# LDO_Regulator.net
KiCad netlist of a schematic drawn in Altium Designer
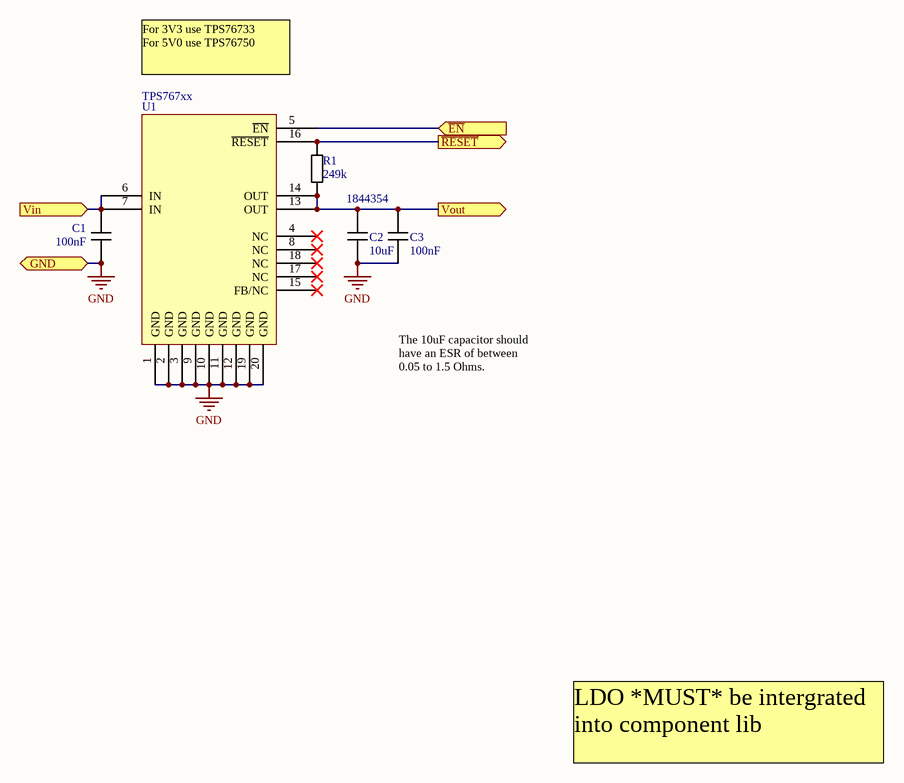
[diagram p0: LDO_Regulator.SchDoc]

(export (version "E")
  (design (tool "Eeschema 10.0.6"))
  (components
    (comp (ref "C1")
      (value "100nF")
      (footprint "0805 Cap")
      (description "0805 MLCC - X7R, 10%")
      (fields (field (name "Comment") "0805 Cap"))
      (libsource (lib "Schlib1") (part "0805 MLCC - X7R, 10%"))
    )
    (comp (ref "C2")
      (value "10uF")
      (footprint "1210 Cap")
      (description "1210 MLCC - X7R, 10%")
      (fields (field (name "SUPPLIER PART NUMBER 1") "1844354") (field (name "Comment") "1210 Cap"))
      (libsource (lib "Schlib1") (part "1210 MLCC - X7R, 10%"))
    )
    (comp (ref "C3")
      (value "100nF")
      (footprint "0805 Cap")
      (description "0805 MLCC - X7R, 10%")
      (fields (field (name "Comment") "0805 Cap"))
      (libsource (lib "Schlib1") (part "0805 MLCC - X7R, 10%"))
    )
    (comp (ref "R1")
      (value "249k")
      (footprint "0805 Resistor")
      (description "0805 Thick Film Resistor 1%")
      (fields (field (name "Comment") "0805 Resistor"))
      (libsource (lib "Schlib1") (part "0805 Thick Film Resistor 1%"))
    )
    (comp (ref "U1")
      (value "TPS767xx")
      (footprint "SOP-20 TPS76700")
      (description "LDO Regulator - ER")
      (libsource (lib "Schlib1") (part "TPS76700"))
    )
  )
  (nets
    (net (code "1") (name "/Vin") (class "Default")
      (node (ref "C1") (pin "2") (pinfunction "2_2") (pintype "passive"))
      (node (ref "U1") (pin "6") (pinfunction "IN_6") (pintype "passive"))
      (node (ref "U1") (pin "7") (pinfunction "IN_7") (pintype "passive"))
    )
    (net (code "2") (name "/Vout") (class "Default")
      (node (ref "C2") (pin "2") (pinfunction "2_2") (pintype "passive"))
      (node (ref "C3") (pin "2") (pinfunction "2_2") (pintype "passive"))
      (node (ref "R1") (pin "1") (pinfunction "1_1") (pintype "passive"))
      (node (ref "U1") (pin "13") (pinfunction "OUT_13") (pintype "passive"))
      (node (ref "U1") (pin "14") (pinfunction "OUT_14") (pintype "passive"))
    )
    (net (code "3") (name "/~{EN}") (class "Default")
      (node (ref "U1") (pin "5") (pinfunction "~{EN}_5") (pintype "passive"))
    )
    (net (code "4") (name "/~{RESET}") (class "Default")
      (node (ref "R1") (pin "2") (pinfunction "2_2") (pintype "passive"))
      (node (ref "U1") (pin "16") (pinfunction "~{RESET}_16") (pintype "passive"))
    )
    (net (code "5") (name "GND") (class "Default")
      (node (ref "C1") (pin "1") (pinfunction "1_1") (pintype "passive"))
      (node (ref "C2") (pin "1") (pinfunction "1_1") (pintype "passive"))
      (node (ref "C3") (pin "1") (pinfunction "1_1") (pintype "passive"))
      (node (ref "U1") (pin "1") (pinfunction "GND_1") (pintype "passive"))
      (node (ref "U1") (pin "10") (pinfunction "GND_10") (pintype "passive"))
      (node (ref "U1") (pin "11") (pinfunction "GND_11") (pintype "passive"))
      (node (ref "U1") (pin "12") (pinfunction "GND_12") (pintype "passive"))
      (node (ref "U1") (pin "19") (pinfunction "GND_19") (pintype "passive"))
      (node (ref "U1") (pin "2") (pinfunction "GND_2") (pintype "passive"))
      (node (ref "U1") (pin "20") (pinfunction "GND_20") (pintype "passive"))
      (node (ref "U1") (pin "3") (pinfunction "GND_3") (pintype "passive"))
      (node (ref "U1") (pin "9") (pinfunction "GND_9") (pintype "passive"))
    )
    (net (code "6") (name "unconnected-(U1-FB{slash}NC-Pad15)") (class "Default")
      (node (ref "U1") (pin "15") (pinfunction "FB/NC_15") (pintype "passive+no_connect"))
    )
    (net (code "7") (name "unconnected-(U1-NC-Pad4)") (class "Default")
      (node (ref "U1") (pin "4") (pinfunction "NC_4") (pintype "passive+no_connect"))
    )
    (net (code "8") (name "unconnected-(U1-NC-Pad8)") (class "Default")
      (node (ref "U1") (pin "8") (pinfunction "NC_8") (pintype "passive+no_connect"))
    )
    (net (code "9") (name "unconnected-(U1-NC-Pad17)") (class "Default")
      (node (ref "U1") (pin "17") (pinfunction "NC_17") (pintype "passive+no_connect"))
    )
    (net (code "10") (name "unconnected-(U1-NC-Pad18)") (class "Default")
      (node (ref "U1") (pin "18") (pinfunction "NC_18") (pintype "passive+no_connect"))
    )
  )
)
